# schem-v1.net
KiCad netlist of a schematic drawn in EAGLE
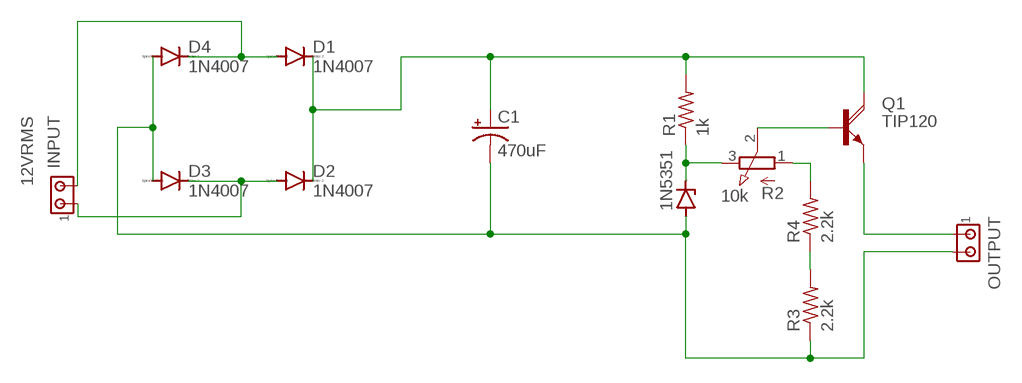
[diagram p0: schematic, sheet 1]

(export (version "E")
  (design (tool "Eeschema 10.0.6"))
  (components
    (comp (ref "1N5351")
      (value "ZENER-DIODEDO41Z10")
      (footprint "eagle-import:DO41Z10")
      (libsource (lib "eagle-import") (part "ZENER-DIODEDO41Z10"))
    )
    (comp (ref "C1")
      (value "470uF")
      (footprint "eagle-import:E3,5-10")
      (libsource (lib "eagle-import") (part "CPOL-USE3.5-10"))
    )
    (comp (ref "D1")
      (value "1N4007")
      (footprint "eagle-import:DO41-10")
      (libsource (lib "eagle-import") (part "1N4004"))
    )
    (comp (ref "D2")
      (value "1N4007")
      (footprint "eagle-import:DO41-10")
      (libsource (lib "eagle-import") (part "1N4004"))
    )
    (comp (ref "D3")
      (value "1N4007")
      (footprint "eagle-import:DO41-10")
      (libsource (lib "eagle-import") (part "1N4004"))
    )
    (comp (ref "D4")
      (value "1N4007")
      (footprint "eagle-import:DO41-10")
      (libsource (lib "eagle-import") (part "1N4004"))
    )
    (comp (ref "INPUT")
      (value "12VRMS")
      (footprint "eagle-import:10X02MTA")
      (fields (field (name "SPICEPREFIX") "I"))
      (libsource (lib "eagle-import") (part "MTA02-100"))
    )
    (comp (ref "OUTPUT")
      (value "MTA02-100")
      (footprint "eagle-import:10X02MTA")
      (libsource (lib "eagle-import") (part "MTA02-100"))
    )
    (comp (ref "Q1")
      (value "TIP120")
      (footprint "eagle-import:TO220AH")
      (libsource (lib "eagle-import") (part "TIP120"))
    )
    (comp (ref "R1")
      (value "1k")
      (footprint "eagle-import:0207_10")
      (libsource (lib "eagle-import") (part "R-US_0207/10"))
    )
    (comp (ref "R2")
      (value "10k")
      (footprint "eagle-import:3RP_1610N")
      (libsource (lib "eagle-import") (part "3RP/1610N"))
    )
    (comp (ref "R3")
      (value "2.2k")
      (footprint "eagle-import:0207_10")
      (libsource (lib "eagle-import") (part "R-US_0207/10"))
    )
    (comp (ref "R4")
      (value "2.2k")
      (footprint "eagle-import:0207_10")
      (libsource (lib "eagle-import") (part "R-US_0207/10"))
    )
  )
  (nets
    (net (code "1") (name "Net-(1N5351-PadA)") (class "Default")
      (node (ref "1N5351") (pin "A") (pinfunction "A_A") (pintype "passive"))
      (node (ref "C1") (pin "-") (pinfunction "-_-") (pintype "passive"))
      (node (ref "D3") (pin "A") (pinfunction "A_A") (pintype "passive"))
      (node (ref "D4") (pin "A") (pinfunction "A_A") (pintype "passive"))
      (node (ref "OUTPUT") (pin "2") (pinfunction "2_2") (pintype "passive"))
      (node (ref "R3") (pin "1") (pinfunction "1_1") (pintype "passive"))
    )
    (net (code "2") (name "Net-(C1-Pad+)") (class "Default")
      (node (ref "C1") (pin "+") (pinfunction "+_+") (pintype "passive"))
      (node (ref "D1") (pin "C") (pinfunction "C_C") (pintype "passive"))
      (node (ref "D2") (pin "C") (pinfunction "C_C") (pintype "passive"))
      (node (ref "Q1") (pin "C") (pinfunction "C_C") (pintype "passive"))
      (node (ref "R1") (pin "2") (pinfunction "2_2") (pintype "passive"))
    )
    (net (code "3") (name "Net-(D1-PadA)") (class "Default")
      (node (ref "D1") (pin "A") (pinfunction "A_A") (pintype "passive"))
      (node (ref "D4") (pin "C") (pinfunction "C_C") (pintype "passive"))
      (node (ref "INPUT") (pin "2") (pinfunction "2_2") (pintype "passive"))
    )
    (net (code "4") (name "Net-(D2-PadA)") (class "Default")
      (node (ref "D2") (pin "A") (pinfunction "A_A") (pintype "passive"))
      (node (ref "D3") (pin "C") (pinfunction "C_C") (pintype "passive"))
      (node (ref "INPUT") (pin "1") (pinfunction "1_1") (pintype "passive"))
    )
    (net (code "5") (name "Net-(OUTPUT-Pad1)") (class "Default")
      (node (ref "OUTPUT") (pin "1") (pinfunction "1_1") (pintype "passive"))
      (node (ref "Q1") (pin "E") (pinfunction "E_E") (pintype "passive"))
    )
    (net (code "6") (name "Net-(R2-A)") (class "Default")
      (node (ref "R2") (pin "1") (pinfunction "A_1") (pintype "passive"))
      (node (ref "R4") (pin "2") (pinfunction "2_2") (pintype "passive"))
    )
    (net (code "7") (name "Net-(R2-E)") (class "Default")
      (node (ref "1N5351") (pin "C") (pinfunction "C_C") (pintype "passive"))
      (node (ref "R1") (pin "1") (pinfunction "1_1") (pintype "passive"))
      (node (ref "R2") (pin "3") (pinfunction "E_3") (pintype "passive"))
    )
    (net (code "8") (name "Net-(R2-S)") (class "Default")
      (node (ref "Q1") (pin "B") (pinfunction "B_B") (pintype "passive"))
      (node (ref "R2") (pin "2") (pinfunction "S_2") (pintype "passive"))
    )
    (net (code "9") (name "Net-(R3-Pad2)") (class "Default")
      (node (ref "R3") (pin "2") (pinfunction "2_2") (pintype "passive"))
      (node (ref "R4") (pin "1") (pinfunction "1_1") (pintype "passive"))
    )
  )
)
